# Source_Selector_V3.net
KiCad netlist of a schematic drawn in Altium Designer
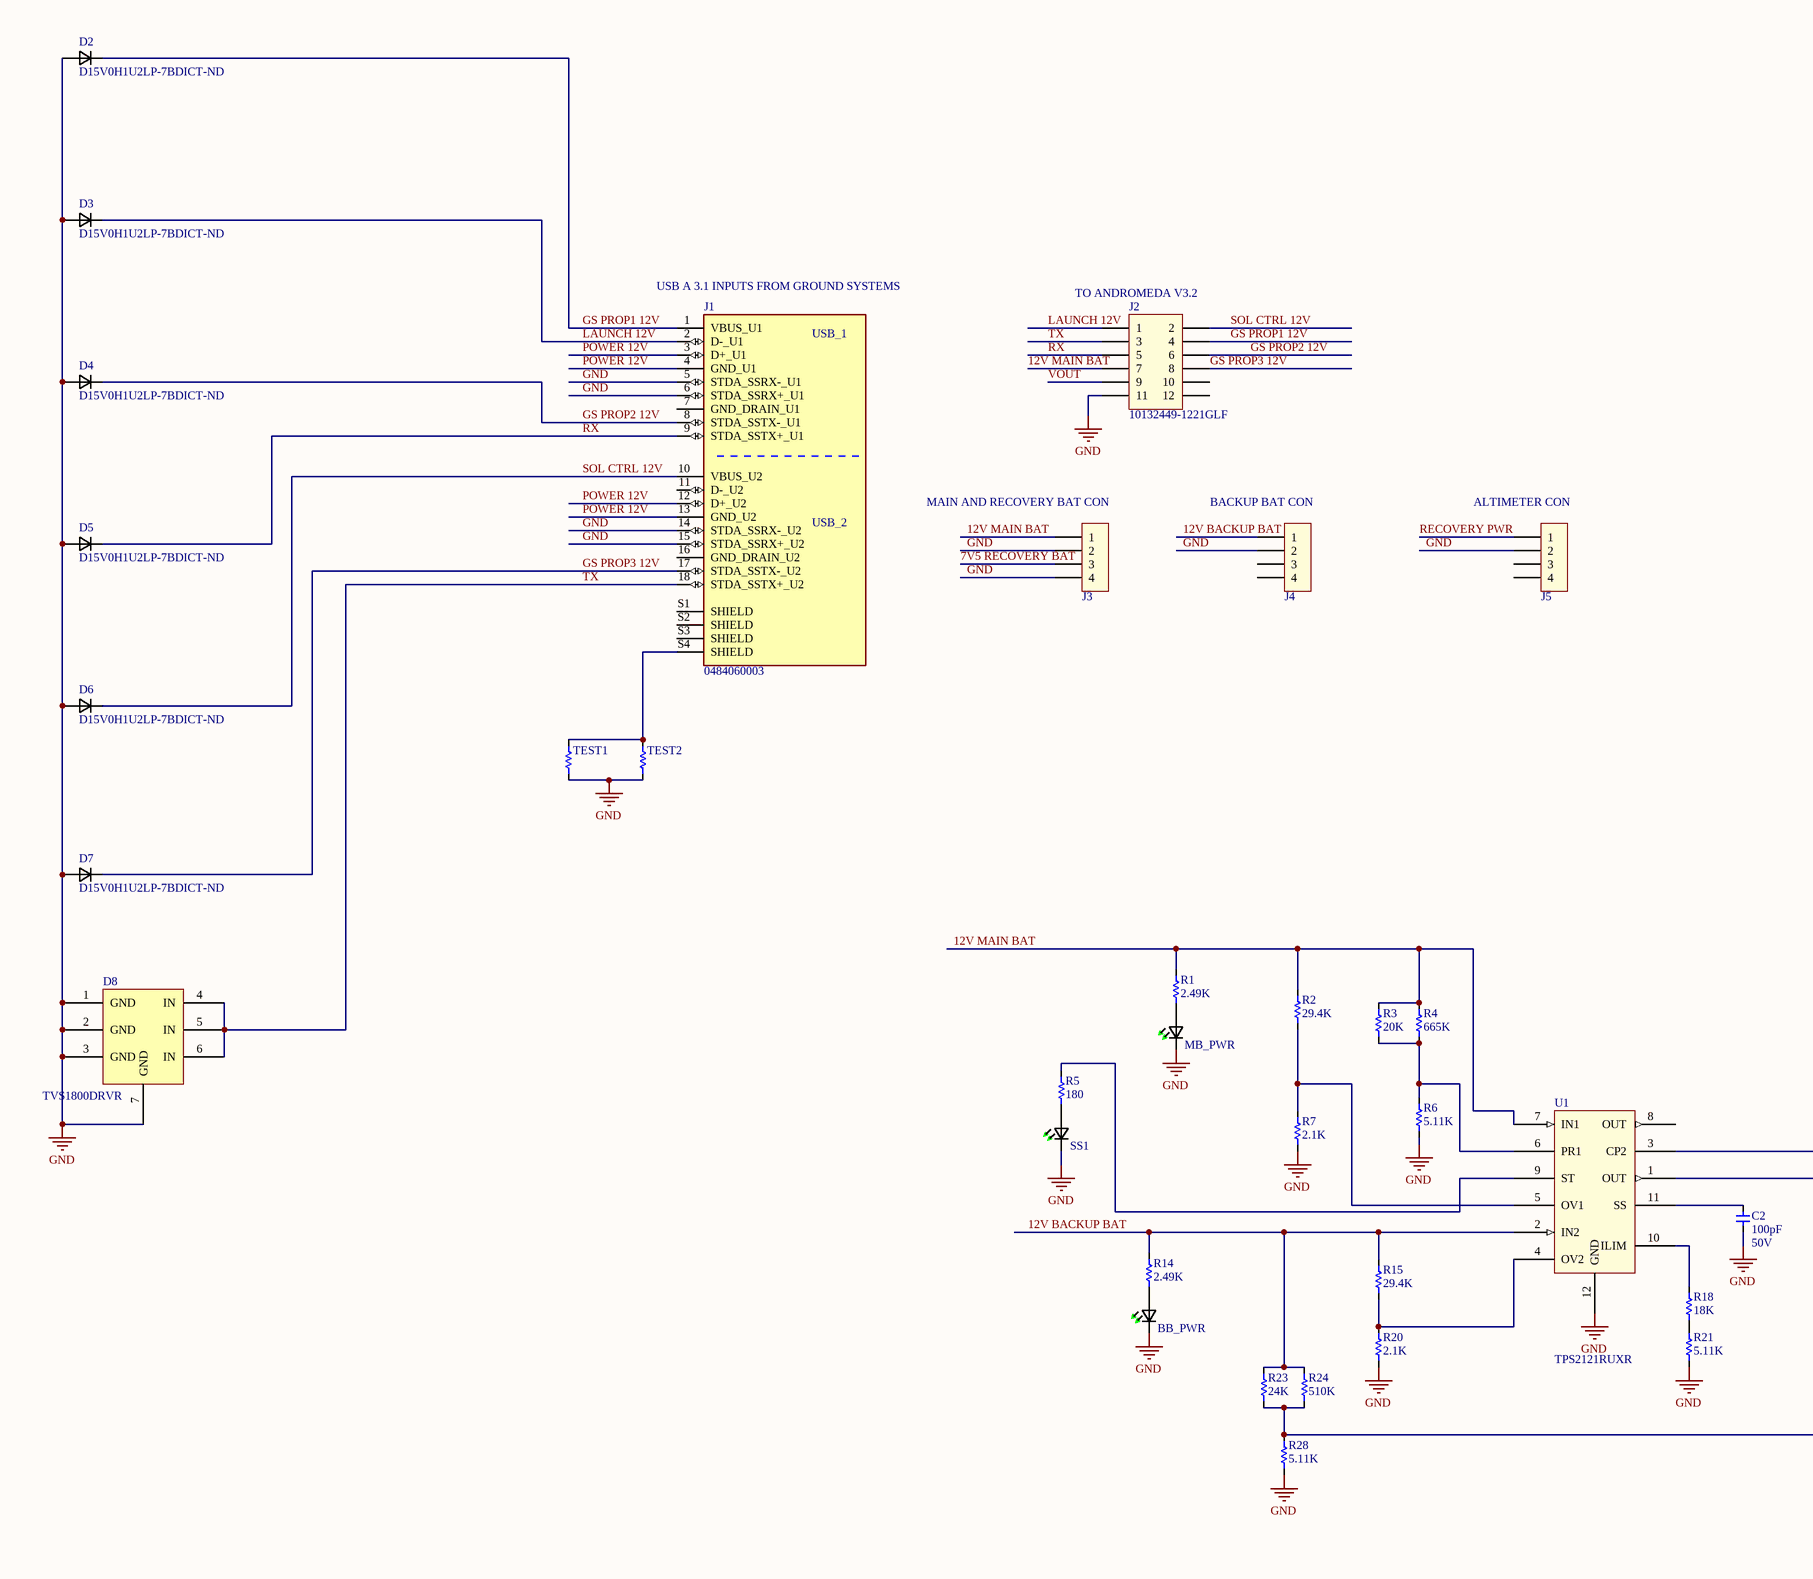
[diagram p0: Source_Selector_V3.SchDoc, left]
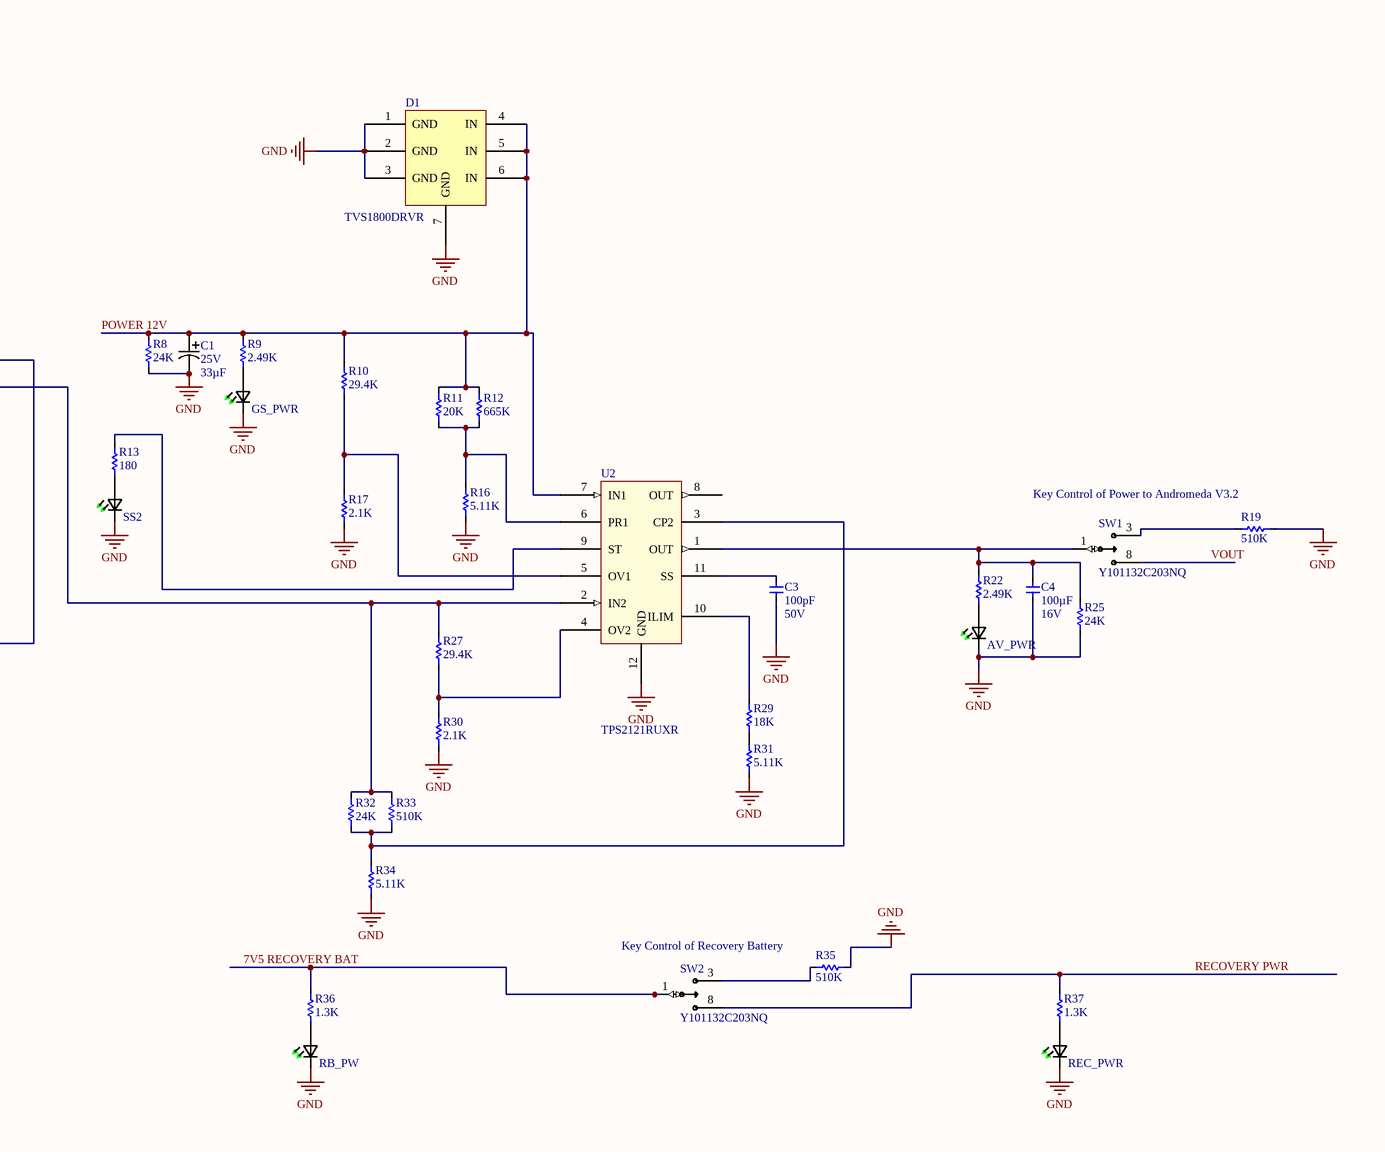
[diagram p1: Source_Selector_V3.SchDoc, right]

(export (version "E")
  (design (tool "Eeschema 10.0.6"))
  (components
    (comp (ref "AV_PWR")
      (value "LTST-C191KGKT")
      (footprint "LTST-C191KGKT")
      (description "LED GREEN CLEAR SMD 0603")
      (fields (field (name "MANUFACTURER") "Lite-On Inc."))
      (libsource (lib "Source Selector") (part "LTST-C191KGKT"))
    )
    (comp (ref "BB_PWR")
      (value "LTST-C191KGKT")
      (footprint "LTST-C191KGKT")
      (description "LED GREEN CLEAR SMD 0603")
      (fields (field (name "MANUFACTURER") "Lite-On Inc."))
      (libsource (lib "Source Selector") (part "LTST-C191KGKT"))
    )
    (comp (ref "C1")
      (value "UZG1E330MCL1GB")
      (footprint "PCAP_6.3x3-ELECT_NCA-M")
      (description "CAP ALUM 33UF 20% 25V SMD")
      (fields
        (field (name "MANUFACTURER") "Nichicon")
        (field (name "VOLTAGE") "25V")
        (field (name "CAPACITANCE") "33µF")
      )
      (libsource (lib "Source Selector") (part "UZG1E330MCL1GB"))
    )
    (comp (ref "C2")
      (value "04025A101JAT2A")
      (footprint "0603[1608]")
      (description "CAP CER 100PF 50V C0G/NP0 0402")
      (fields
        (field (name "MANUFACTURER") "AVX Corporation")
        (field (name "TOLERANCE") "±5%")
        (field (name "CAPACITANCE") "100pF")
        (field (name "VOLTAGE - RATED") "50V")
      )
      (libsource (lib "Source Selector") (part "04025A101JAT2A"))
    )
    (comp (ref "C3")
      (value "04025A101JAT2A")
      (footprint "0603[1608]")
      (description "CAP CER 100PF 50V C0G/NP0 0402")
      (fields
        (field (name "MANUFACTURER") "AVX Corporation")
        (field (name "TOLERANCE") "±5%")
        (field (name "CAPACITANCE") "100pF")
        (field (name "VOLTAGE - RATED") "50V")
      )
      (libsource (lib "Source Selector") (part "04025A101JAT2A"))
    )
    (comp (ref "C4")
      (value "EMK325ABJ107MM-P")
      (footprint "CAPC3225X280N")
      (description "CAP CER 100UF 16V X5R 1210")
      (fields
        (field (name "MANUFACTURER") "Taiyo Yuden")
        (field (name "TOLERANCE") "±20%")
        (field (name "CAPACITANCE") "100µF")
        (field (name "VOLTAGE - RATED") "16V")
      )
      (libsource (lib "Source Selector") (part "EMK325ABJ107MM-P"))
    )
    (comp (ref "D1")
      (value "TVS1800DRVR")
      (footprint "TVS1800DRVR")
      (description "UNIDIR PRECISION SURGE DIODE")
      (libsource (lib "Source Selector") (part "TVS1800DRVR"))
    )
    (comp (ref "D2")
      (value "D15V0H1U2LP-7B")
      (footprint "04025A101JAT2A")
      (description "TVS DIODE 15VWM 27VC DFN1006-2")
      (fields
        (field (name "MANUFACTURER") "Diodes Incorporated")
        (field (name "SUPPLIER PART NUMBER 1") "D15V0H1U2LP-7BDICT-ND")
      )
      (libsource (lib "Source Selector") (part "D15V0H1U2LP-7B"))
    )
    (comp (ref "D3")
      (value "D15V0H1U2LP-7B")
      (footprint "04025A101JAT2A")
      (description "TVS DIODE 15VWM 27VC DFN1006-2")
      (fields
        (field (name "MANUFACTURER") "Diodes Incorporated")
        (field (name "SUPPLIER PART NUMBER 1") "D15V0H1U2LP-7BDICT-ND")
      )
      (libsource (lib "Source Selector") (part "D15V0H1U2LP-7B"))
    )
    (comp (ref "D4")
      (value "D15V0H1U2LP-7B")
      (footprint "04025A101JAT2A")
      (description "TVS DIODE 15VWM 27VC DFN1006-2")
      (fields
        (field (name "MANUFACTURER") "Diodes Incorporated")
        (field (name "SUPPLIER PART NUMBER 1") "D15V0H1U2LP-7BDICT-ND")
      )
      (libsource (lib "Source Selector") (part "D15V0H1U2LP-7B"))
    )
    (comp (ref "D5")
      (value "D15V0H1U2LP-7B")
      (footprint "04025A101JAT2A")
      (description "TVS DIODE 15VWM 27VC DFN1006-2")
      (fields
        (field (name "MANUFACTURER") "Diodes Incorporated")
        (field (name "SUPPLIER PART NUMBER 1") "D15V0H1U2LP-7BDICT-ND")
      )
      (libsource (lib "Source Selector") (part "D15V0H1U2LP-7B"))
    )
    (comp (ref "D6")
      (value "D15V0H1U2LP-7B")
      (footprint "04025A101JAT2A")
      (description "TVS DIODE 15VWM 27VC DFN1006-2")
      (fields
        (field (name "MANUFACTURER") "Diodes Incorporated")
        (field (name "SUPPLIER PART NUMBER 1") "D15V0H1U2LP-7BDICT-ND")
      )
      (libsource (lib "Source Selector") (part "D15V0H1U2LP-7B"))
    )
    (comp (ref "D7")
      (value "D15V0H1U2LP-7B")
      (footprint "04025A101JAT2A")
      (description "TVS DIODE 15VWM 27VC DFN1006-2")
      (fields
        (field (name "MANUFACTURER") "Diodes Incorporated")
        (field (name "SUPPLIER PART NUMBER 1") "D15V0H1U2LP-7BDICT-ND")
      )
      (libsource (lib "Source Selector") (part "D15V0H1U2LP-7B"))
    )
    (comp (ref "D8")
      (value "TVS1800DRVR")
      (footprint "TVS1800DRVR")
      (description "UNIDIR PRECISION SURGE DIODE")
      (libsource (lib "Source Selector") (part "TVS1800DRVR"))
    )
    (comp (ref "GS_PWR")
      (value "LTST-C191KGKT")
      (footprint "LTST-C191KGKT")
      (description "LED GREEN CLEAR SMD 0603")
      (fields (field (name "MANUFACTURER") "Lite-On Inc."))
      (libsource (lib "Source Selector") (part "LTST-C191KGKT"))
    )
    (comp (ref "J1")
      (value "0484060003")
      (footprint "SnapEDApcb:MOLEX_0484060003")
      (fields (field (name "MF") "Molex"))
      (libsource (lib "Source Selector") (part "0484060003"))
    )
    (comp (ref "J2")
      (value "10132449-1221GLF")
      (footprint "10132449-1221GLF")
      (description "CONN HEADER R/A 12POS 3MM")
      (fields (field (name "MANUFACTURER") "Amphenol ICC (FCI)"))
      (libsource (lib "Source Selector") (part "10132449-1221GLF"))
    )
    (comp (ref "J3")
      (value "0430450400")
      (footprint "0430450400")
      (description "CONN HEADER R/A 4POS 3MM")
      (fields (field (name "MANUFACTURER") "Molex"))
      (libsource (lib "Source Selector") (part "0430450400"))
    )
    (comp (ref "J4")
      (value "0430450400")
      (footprint "0430450400")
      (description "CONN HEADER R/A 4POS 3MM")
      (fields (field (name "MANUFACTURER") "Molex"))
      (libsource (lib "Source Selector") (part "0430450400"))
    )
    (comp (ref "J5")
      (value "0430450400")
      (footprint "0430450400")
      (description "CONN HEADER R/A 4POS 3MM")
      (fields (field (name "MANUFACTURER") "Molex"))
      (libsource (lib "Source Selector") (part "0430450400"))
    )
    (comp (ref "MB_PWR")
      (value "LTST-C191KGKT")
      (footprint "LTST-C191KGKT")
      (description "LED GREEN CLEAR SMD 0603")
      (fields (field (name "MANUFACTURER") "Lite-On Inc."))
      (libsource (lib "Source Selector") (part "LTST-C191KGKT"))
    )
    (comp (ref "R1")
      (value "ERA-3AEB2491V")
      (footprint "0603[1608]")
      (description "RES SMD 2.49KOHM 0.1% 1/10W 0603")
      (fields
        (field (name "TOLERANCE") "±0.1%")
        (field (name "MANUFACTURER") "Panasonic Electronic Components")
        (field (name "RESISTANCE") "2.49K")
      )
      (libsource (lib "Source Selector") (part "ERA-3AEB2491V"))
    )
    (comp (ref "R2")
      (value "RMCF0603FT29K4")
      (footprint "0603[1608]")
      (description "RES 29.4K OHM 1% 1/10W 0603")
      (fields
        (field (name "TOLERANCE") "±1%")
        (field (name "MANUFACTURER") "Stackpole Electronics Inc")
        (field (name "RESISTANCE") "29.4K")
      )
      (libsource (lib "Source Selector") (part "RMCF0603FT29K4"))
    )
    (comp (ref "R3")
      (value "RNCF0603BTC20K0")
      (footprint "0603[1608]")
      (description "RES 20K OHM 0.1% 1/10W 0603")
      (fields
        (field (name "TOLERANCE") "±0.1%")
        (field (name "MANUFACTURER") "Stackpole Electronics Inc")
        (field (name "RESISTANCE") "20K")
      )
      (libsource (lib "Source Selector") (part "RNCF0603BTC20K0"))
    )
    (comp (ref "R4")
      (value "RMCF0603FT665K")
      (footprint "0603[1608]")
      (description "RES 665K OHM 1% 1/10W 0603")
      (fields
        (field (name "TOLERANCE") "±1%")
        (field (name "MANUFACTURER") "Stackpole Electronics Inc")
        (field (name "RESISTANCE") "665K")
      )
      (libsource (lib "Source Selector") (part "RMCF0603FT665K"))
    )
    (comp (ref "R5")
      (value "CRGCQ0603F180R")
      (footprint "0603[1608]")
      (description "RES 180 OHM 1% 1/10W 0603")
      (fields
        (field (name "TOLERANCE") "±0.1%")
        (field (name "MANUFACTURER") "TE Connectivity Passive Product")
        (field (name "RESISTANCE") "180")
      )
      (libsource (lib "Source Selector") (part "CRGCQ0603F180R"))
    )
    (comp (ref "R6")
      (value "RT0603BRD075K11L")
      (footprint "0603[1608]")
      (description "RES SMD 5.11KOHM 0.1% 1/10W 0603")
      (fields
        (field (name "TOLERANCE") "±0.1%")
        (field (name "MANUFACTURER") "Yageo")
        (field (name "RESISTANCE") "5.11K")
      )
      (libsource (lib "Source Selector") (part "RT0603BRD075K11L"))
    )
    (comp (ref "R7")
      (value "RQ73C1J2K1BTD")
      (footprint "0603[1608]")
      (description "RES 2.1 KOHMS 0.1% 0.15W 0603")
      (fields
        (field (name "TOLERANCE") "±0.1%")
        (field (name "MANUFACTURER") "TE Connectivity Passive Product")
        (field (name "RESISTANCE") "2.1K")
      )
      (libsource (lib "Source Selector") (part "RQ73C1J2K1BTD"))
    )
    (comp (ref "R8")
      (value "RT0603BRD0724KL")
      (footprint "0603[1608]")
      (description "RES SMD 24K OHM 0.1% 1/10W 0603")
      (fields
        (field (name "TOLERANCE") "±0.1%")
        (field (name "MANUFACTURER") "Yageo")
        (field (name "RESISTANCE") "24K")
      )
      (libsource (lib "Source Selector") (part "RT0603BRD0724KL"))
    )
    (comp (ref "R9")
      (value "ERA-3AEB2491V")
      (footprint "0603[1608]")
      (description "RES SMD 2.49KOHM 0.1% 1/10W 0603")
      (fields
        (field (name "TOLERANCE") "±0.1%")
        (field (name "MANUFACTURER") "Panasonic Electronic Components")
        (field (name "RESISTANCE") "2.49K")
      )
      (libsource (lib "Source Selector") (part "ERA-3AEB2491V"))
    )
    (comp (ref "R10")
      (value "RMCF0603FT29K4")
      (footprint "0603[1608]")
      (description "RES 29.4K OHM 1% 1/10W 0603")
      (fields
        (field (name "TOLERANCE") "±1%")
        (field (name "MANUFACTURER") "Stackpole Electronics Inc")
        (field (name "RESISTANCE") "29.4K")
      )
      (libsource (lib "Source Selector") (part "RMCF0603FT29K4"))
    )
    (comp (ref "R11")
      (value "RNCF0603BTC20K0")
      (footprint "0603[1608]")
      (description "RES 20K OHM 0.1% 1/10W 0603")
      (fields
        (field (name "TOLERANCE") "±0.1%")
        (field (name "MANUFACTURER") "Stackpole Electronics Inc")
        (field (name "RESISTANCE") "20K")
      )
      (libsource (lib "Source Selector") (part "RNCF0603BTC20K0"))
    )
    (comp (ref "R12")
      (value "RMCF0603FT665K")
      (footprint "0603[1608]")
      (description "RES 665K OHM 1% 1/10W 0603")
      (fields
        (field (name "TOLERANCE") "±1%")
        (field (name "MANUFACTURER") "Stackpole Electronics Inc")
        (field (name "RESISTANCE") "665K")
      )
      (libsource (lib "Source Selector") (part "RMCF0603FT665K"))
    )
    (comp (ref "R13")
      (value "CRGCQ0603F180R")
      (footprint "0603[1608]")
      (description "RES 180 OHM 1% 1/10W 0603")
      (fields
        (field (name "TOLERANCE") "±0.1%")
        (field (name "MANUFACTURER") "TE Connectivity Passive Product")
        (field (name "RESISTANCE") "180")
      )
      (libsource (lib "Source Selector") (part "CRGCQ0603F180R"))
    )
    (comp (ref "R14")
      (value "ERA-3AEB2491V")
      (footprint "0603[1608]")
      (description "RES SMD 2.49KOHM 0.1% 1/10W 0603")
      (fields
        (field (name "TOLERANCE") "±0.1%")
        (field (name "MANUFACTURER") "Panasonic Electronic Components")
        (field (name "RESISTANCE") "2.49K")
      )
      (libsource (lib "Source Selector") (part "ERA-3AEB2491V"))
    )
    (comp (ref "R15")
      (value "RMCF0603FT29K4")
      (footprint "0603[1608]")
      (description "RES 29.4K OHM 1% 1/10W 0603")
      (fields
        (field (name "TOLERANCE") "±1%")
        (field (name "MANUFACTURER") "Stackpole Electronics Inc")
        (field (name "RESISTANCE") "29.4K")
      )
      (libsource (lib "Source Selector") (part "RMCF0603FT29K4"))
    )
    (comp (ref "R16")
      (value "RT0603BRD075K11L")
      (footprint "0603[1608]")
      (description "RES SMD 5.11KOHM 0.1% 1/10W 0603")
      (fields
        (field (name "TOLERANCE") "±0.1%")
        (field (name "MANUFACTURER") "Yageo")
        (field (name "RESISTANCE") "5.11K")
      )
      (libsource (lib "Source Selector") (part "RT0603BRD075K11L"))
    )
    (comp (ref "R17")
      (value "RQ73C1J2K1BTD")
      (footprint "0603[1608]")
      (description "RES 2.1 KOHMS 0.1% 0.15W 0603")
      (fields
        (field (name "TOLERANCE") "±0.1%")
        (field (name "MANUFACTURER") "TE Connectivity Passive Product")
        (field (name "RESISTANCE") "2.1K")
      )
      (libsource (lib "Source Selector") (part "RQ73C1J2K1BTD"))
    )
    (comp (ref "R18")
      (value "RT0603BRE0718KL")
      (footprint "0603[1608]")
      (description "RES SMD 18K OHM 0.1% 1/10W 0603")
      (fields
        (field (name "TOLERANCE") "±0.1%")
        (field (name "MANUFACTURER") "Yageo")
        (field (name "RESISTANCE") "18K")
      )
      (libsource (lib "Source Selector") (part "RT0603BRE0718KL"))
    )
    (comp (ref "R19")
      (value "CPF0603B510KE1")
      (footprint "0603[1608]")
      (description "RES SMD 510K OHM 0.1% 1/16W 0603")
      (fields
        (field (name "TOLERANCE") "±0.1%")
        (field (name "MANUFACTURER") "TE Connectivity Passive Product")
        (field (name "RESISTANCE") "510K")
      )
      (libsource (lib "Source Selector") (part "CPF0603B510KE1"))
    )
    (comp (ref "R20")
      (value "RQ73C1J2K1BTD")
      (footprint "0603[1608]")
      (description "RES 2.1 KOHMS 0.1% 0.15W 0603")
      (fields
        (field (name "TOLERANCE") "±0.1%")
        (field (name "MANUFACTURER") "TE Connectivity Passive Product")
        (field (name "RESISTANCE") "2.1K")
      )
      (libsource (lib "Source Selector") (part "RQ73C1J2K1BTD"))
    )
    (comp (ref "R21")
      (value "RT0603BRD075K11L")
      (footprint "0603[1608]")
      (description "RES SMD 5.11KOHM 0.1% 1/10W 0603")
      (fields
        (field (name "TOLERANCE") "±0.1%")
        (field (name "MANUFACTURER") "Yageo")
        (field (name "RESISTANCE") "5.11K")
      )
      (libsource (lib "Source Selector") (part "RT0603BRD075K11L"))
    )
    (comp (ref "R22")
      (value "ERA-3AEB2491V")
      (footprint "0603[1608]")
      (description "RES SMD 2.49KOHM 0.1% 1/10W 0603")
      (fields
        (field (name "TOLERANCE") "±0.1%")
        (field (name "MANUFACTURER") "Panasonic Electronic Components")
        (field (name "RESISTANCE") "2.49K")
      )
      (libsource (lib "Source Selector") (part "ERA-3AEB2491V"))
    )
    (comp (ref "R23")
      (value "RT0603BRD0724KL")
      (footprint "0603[1608]")
      (description "RES SMD 24K OHM 0.1% 1/10W 0603")
      (fields
        (field (name "TOLERANCE") "±0.1%")
        (field (name "MANUFACTURER") "Yageo")
        (field (name "RESISTANCE") "24K")
      )
      (libsource (lib "Source Selector") (part "RT0603BRD0724KL"))
    )
    (comp (ref "R24")
      (value "CPF0603B510KE1")
      (footprint "0603[1608]")
      (description "RES SMD 510K OHM 0.1% 1/16W 0603")
      (fields
        (field (name "TOLERANCE") "±0.1%")
        (field (name "MANUFACTURER") "TE Connectivity Passive Product")
        (field (name "RESISTANCE") "510K")
      )
      (libsource (lib "Source Selector") (part "CPF0603B510KE1"))
    )
    (comp (ref "R25")
      (value "RT0603BRD0724KL")
      (footprint "0603[1608]")
      (description "RES SMD 24K OHM 0.1% 1/10W 0603")
      (fields
        (field (name "TOLERANCE") "±0.1%")
        (field (name "MANUFACTURER") "Yageo")
        (field (name "RESISTANCE") "24K")
      )
      (libsource (lib "Source Selector") (part "RT0603BRD0724KL"))
    )
    (comp (ref "R27")
      (value "RMCF0603FT29K4")
      (footprint "0603[1608]")
      (description "RES 29.4K OHM 1% 1/10W 0603")
      (fields
        (field (name "TOLERANCE") "±1%")
        (field (name "MANUFACTURER") "Stackpole Electronics Inc")
        (field (name "RESISTANCE") "29.4K")
      )
      (libsource (lib "Source Selector") (part "RMCF0603FT29K4"))
    )
    (comp (ref "R28")
      (value "RT0603BRD075K11L")
      (footprint "0603[1608]")
      (description "RES SMD 5.11KOHM 0.1% 1/10W 0603")
      (fields
        (field (name "TOLERANCE") "±0.1%")
        (field (name "MANUFACTURER") "Yageo")
        (field (name "RESISTANCE") "5.11K")
      )
      (libsource (lib "Source Selector") (part "RT0603BRD075K11L"))
    )
    (comp (ref "R29")
      (value "RT0603BRE0718KL")
      (footprint "0603[1608]")
      (description "RES SMD 18K OHM 0.1% 1/10W 0603")
      (fields
        (field (name "TOLERANCE") "±0.1%")
        (field (name "MANUFACTURER") "Yageo")
        (field (name "RESISTANCE") "18K")
      )
      (libsource (lib "Source Selector") (part "RT0603BRE0718KL"))
    )
    (comp (ref "R30")
      (value "RQ73C1J2K1BTD")
      (footprint "0603[1608]")
      (description "RES 2.1 KOHMS 0.1% 0.15W 0603")
      (fields
        (field (name "TOLERANCE") "±0.1%")
        (field (name "MANUFACTURER") "TE Connectivity Passive Product")
        (field (name "RESISTANCE") "2.1K")
      )
      (libsource (lib "Source Selector") (part "RQ73C1J2K1BTD"))
    )
    (comp (ref "R31")
      (value "RT0603BRD075K11L")
      (footprint "0603[1608]")
      (description "RES SMD 5.11KOHM 0.1% 1/10W 0603")
      (fields
        (field (name "TOLERANCE") "±0.1%")
        (field (name "MANUFACTURER") "Yageo")
        (field (name "RESISTANCE") "5.11K")
      )
      (libsource (lib "Source Selector") (part "RT0603BRD075K11L"))
    )
    (comp (ref "R32")
      (value "RT0603BRD0724KL")
      (footprint "0603[1608]")
      (description "RES SMD 24K OHM 0.1% 1/10W 0603")
      (fields
        (field (name "TOLERANCE") "±0.1%")
        (field (name "MANUFACTURER") "Yageo")
        (field (name "RESISTANCE") "24K")
      )
      (libsource (lib "Source Selector") (part "RT0603BRD0724KL"))
    )
    (comp (ref "R33")
      (value "CPF0603B510KE1")
      (footprint "0603[1608]")
      (description "RES SMD 510K OHM 0.1% 1/16W 0603")
      (fields
        (field (name "TOLERANCE") "±0.1%")
        (field (name "MANUFACTURER") "TE Connectivity Passive Product")
        (field (name "RESISTANCE") "510K")
      )
      (libsource (lib "Source Selector") (part "CPF0603B510KE1"))
    )
    (comp (ref "R34")
      (value "RT0603BRD075K11L")
      (footprint "0603[1608]")
      (description "RES SMD 5.11KOHM 0.1% 1/10W 0603")
      (fields
        (field (name "TOLERANCE") "±0.1%")
        (field (name "MANUFACTURER") "Yageo")
        (field (name "RESISTANCE") "5.11K")
      )
      (libsource (lib "Source Selector") (part "RT0603BRD075K11L"))
    )
    (comp (ref "R35")
      (value "CPF0603B510KE1")
      (footprint "0603[1608]")
      (description "RES SMD 510K OHM 0.1% 1/16W 0603")
      (fields
        (field (name "TOLERANCE") "±0.1%")
        (field (name "MANUFACTURER") "TE Connectivity Passive Product")
        (field (name "RESISTANCE") "510K")
      )
      (libsource (lib "Source Selector") (part "CPF0603B510KE1"))
    )
    (comp (ref "R36")
      (value "MCT06030C1301FP500")
      (footprint "0603[1608]")
      (description "RES SMD 1.3K OHM 1% 1/8W 0603")
      (fields
        (field (name "TOLERANCE") "±1%")
        (field (name "MANUFACTURER") "Vishay Beyschlag")
        (field (name "RESISTANCE") "1.3K")
      )
      (libsource (lib "Source Selector") (part "MCT06030C1301FP500"))
    )
    (comp (ref "R37")
      (value "MCT06030C1301FP500")
      (footprint "0603[1608]")
      (description "RES SMD 1.3K OHM 1% 1/8W 0603")
      (fields
        (field (name "TOLERANCE") "±1%")
        (field (name "MANUFACTURER") "Vishay Beyschlag")
        (field (name "RESISTANCE") "1.3K")
      )
      (libsource (lib "Source Selector") (part "MCT06030C1301FP500"))
    )
    (comp (ref "RB_PW")
      (value "LTST-C191KGKT")
      (footprint "LTST-C191KGKT")
      (description "LED GREEN CLEAR SMD 0603")
      (fields (field (name "MANUFACTURER") "Lite-On Inc."))
      (libsource (lib "Source Selector") (part "LTST-C191KGKT"))
    )
    (comp (ref "REC_PWR")
      (value "LTST-C191KGKT")
      (footprint "LTST-C191KGKT")
      (description "LED GREEN CLEAR SMD 0603")
      (fields (field (name "MANUFACTURER") "Lite-On Inc."))
      (libsource (lib "Source Selector") (part "LTST-C191KGKT"))
    )
    (comp (ref "SS1")
      (value "LTST-C191KGKT")
      (footprint "LTST-C191KGKT")
      (description "LED GREEN CLEAR SMD 0603")
      (fields (field (name "MANUFACTURER") "Lite-On Inc."))
      (libsource (lib "Source Selector") (part "LTST-C191KGKT"))
    )
    (comp (ref "SS2")
      (value "LTST-C191KGKT")
      (footprint "LTST-C191KGKT")
      (description "LED GREEN CLEAR SMD 0603")
      (fields (field (name "MANUFACTURER") "Lite-On Inc."))
      (libsource (lib "Source Selector") (part "LTST-C191KGKT"))
    )
    (comp (ref "SW1")
      (value "Y101132C203NQ")
      (footprint "Y101132C203NQ")
      (description "SWITCH KEYLOCK 2POS SPDT 4A 125V")
      (fields (field (name "MANUFACTURER") "C&K"))
      (libsource (lib "Source Selector") (part "Y101132C203NQ"))
    )
    (comp (ref "SW2")
      (value "Y101132C203NQ")
      (footprint "Y101132C203NQ")
      (description "SWITCH KEYLOCK 2POS SPDT 4A 125V")
      (fields (field (name "MANUFACTURER") "C&K"))
      (libsource (lib "Source Selector") (part "Y101132C203NQ"))
    )
    (comp (ref "TEST1")
      (value "RQ73C1J2K1BTD")
      (footprint "0603[1608]")
      (description "RES 2.1 KOHMS 0.1% 0.15W 0603")
      (fields
        (field (name "TOLERANCE") "±0.1%")
        (field (name "MANUFACTURER") "TE Connectivity Passive Product")
      )
      (libsource (lib "Source Selector") (part "RQ73C1J2K1BTD"))
    )
    (comp (ref "TEST2")
      (value "RQ73C1J2K1BTD")
      (footprint "0603[1608]")
      (description "RES 2.1 KOHMS 0.1% 0.15W 0603")
      (fields
        (field (name "TOLERANCE") "±0.1%")
        (field (name "MANUFACTURER") "TE Connectivity Passive Product")
      )
      (libsource (lib "Source Selector") (part "RQ73C1J2K1BTD"))
    )
    (comp (ref "U1")
      (value "TPS2121RUXR")
      (footprint "IC_TPS2121RUXR")
      (description "PWR MGMT BATTERY MGMT")
      (libsource (lib "Source Selector") (part "TPS2121RUXR"))
    )
    (comp (ref "U2")
      (value "TPS2121RUXR")
      (footprint "IC_TPS2121RUXR")
      (description "PWR MGMT BATTERY MGMT")
      (libsource (lib "Source Selector") (part "TPS2121RUXR"))
    )
  )
  (nets
    (net (code "1") (name "/7V5 RECOVERY BAT") (class "Default")
      (node (ref "J3") (pin "3") (pinfunction "3_3") (pintype "passive"))
      (node (ref "R36") (pin "2") (pinfunction "2_2") (pintype "passive"))
      (node (ref "SW2") (pin "1") (pinfunction "1_1") (pintype "bidirectional"))
    )
    (net (code "2") (name "/12V BACKUP BAT") (class "Default")
      (node (ref "J4") (pin "1") (pinfunction "1_1") (pintype "passive"))
      (node (ref "R14") (pin "2") (pinfunction "2_2") (pintype "passive"))
      (node (ref "R15") (pin "2") (pinfunction "2_2") (pintype "passive"))
      (node (ref "R23") (pin "2") (pinfunction "2_2") (pintype "passive"))
      (node (ref "R24") (pin "2") (pinfunction "2_2") (pintype "passive"))
      (node (ref "U1") (pin "2") (pinfunction "IN2_2") (pintype "input"))
    )
    (net (code "3") (name "/12V MAIN BAT") (class "Default")
      (node (ref "J2") (pin "7") (pinfunction "7_7") (pintype "passive"))
      (node (ref "J3") (pin "1") (pinfunction "1_1") (pintype "passive"))
      (node (ref "R1") (pin "2") (pinfunction "2_2") (pintype "passive"))
      (node (ref "R2") (pin "2") (pinfunction "2_2") (pintype "passive"))
      (node (ref "R3") (pin "2") (pinfunction "2_2") (pintype "passive"))
      (node (ref "R4") (pin "2") (pinfunction "2_2") (pintype "passive"))
      (node (ref "U1") (pin "7") (pinfunction "IN1_7") (pintype "input"))
    )
    (net (code "4") (name "/GS PROP1 12V") (class "Default")
      (node (ref "D2") (pin "1") (pinfunction "K2_1") (pintype "passive"))
      (node (ref "J1") (pin "1") (pinfunction "VBUS_U1_1") (pintype "power_in"))
      (node (ref "J2") (pin "4") (pinfunction "4_4") (pintype "passive"))
    )
    (net (code "5") (name "/GS PROP2 12V") (class "Default")
      (node (ref "D4") (pin "1") (pinfunction "K2_1") (pintype "passive"))
      (node (ref "J1") (pin "8") (pinfunction "STDA_SSTX-_U1_8") (pintype "bidirectional"))
      (node (ref "J2") (pin "6") (pinfunction "6_6") (pintype "passive"))
    )
    (net (code "6") (name "/GS PROP3 12V") (class "Default")
      (node (ref "D7") (pin "1") (pinfunction "K2_1") (pintype "passive"))
      (node (ref "J1") (pin "17") (pinfunction "STDA_SSTX-_U2_17") (pintype "bidirectional"))
      (node (ref "J2") (pin "8") (pinfunction "8_8") (pintype "passive"))
    )
    (net (code "7") (name "/LAUNCH 12V") (class "Default")
      (node (ref "D3") (pin "1") (pinfunction "K2_1") (pintype "passive"))
      (node (ref "J1") (pin "2") (pinfunction "D-_U1_2") (pintype "bidirectional"))
      (node (ref "J2") (pin "1") (pinfunction "1_1") (pintype "passive"))
    )
    (net (code "8") (name "/POWER 12V") (class "Default")
      (node (ref "C1") (pin "1") (pinfunction "1_1") (pintype "passive"))
      (node (ref "D1") (pin "4") (pinfunction "IN_4") (pintype "passive"))
      (node (ref "D1") (pin "5") (pinfunction "IN_5") (pintype "passive"))
      (node (ref "D1") (pin "6") (pinfunction "IN_6") (pintype "passive"))
      (node (ref "J1") (pin "12") (pinfunction "D+_U2_12") (pintype "bidirectional"))
      (node (ref "J1") (pin "13") (pinfunction "GND_U2_13") (pintype "power_in"))
      (node (ref "J1") (pin "3") (pinfunction "D+_U1_3") (pintype "bidirectional"))
      (node (ref "J1") (pin "4") (pinfunction "GND_U1_4") (pintype "power_in"))
      (node (ref "R10") (pin "2") (pinfunction "2_2") (pintype "passive"))
      (node (ref "R11") (pin "2") (pinfunction "2_2") (pintype "passive"))
      (node (ref "R12") (pin "2") (pinfunction "2_2") (pintype "passive"))
      (node (ref "R8") (pin "2") (pinfunction "2_2") (pintype "passive"))
      (node (ref "R9") (pin "2") (pinfunction "2_2") (pintype "passive"))
      (node (ref "U2") (pin "7") (pinfunction "IN1_7") (pintype "input"))
    )
    (net (code "9") (name "/RECOVERY PWR") (class "Default")
      (node (ref "J5") (pin "1") (pinfunction "1_1") (pintype "passive"))
      (node (ref "R37") (pin "2") (pinfunction "2_2") (pintype "passive"))
      (node (ref "SW2") (pin "8") (pinfunction "8_8") (pintype "power_in"))
    )
    (net (code "10") (name "/RX") (class "Default")
      (node (ref "D5") (pin "1") (pinfunction "K2_1") (pintype "passive"))
      (node (ref "J1") (pin "9") (pinfunction "STDA_SSTX+_U1_9") (pintype "bidirectional"))
      (node (ref "J2") (pin "5") (pinfunction "5_5") (pintype "passive"))
    )
    (net (code "11") (name "/SOL CTRL 12V") (class "Default")
      (node (ref "D6") (pin "1") (pinfunction "K2_1") (pintype "passive"))
      (node (ref "J1") (pin "10") (pinfunction "VBUS_U2_10") (pintype "power_in"))
      (node (ref "J2") (pin "2") (pinfunction "2_2") (pintype "passive"))
    )
    (net (code "12") (name "/TX") (class "Default")
      (node (ref "D8") (pin "4") (pinfunction "IN_4") (pintype "passive"))
      (node (ref "D8") (pin "5") (pinfunction "IN_5") (pintype "passive"))
      (node (ref "D8") (pin "6") (pinfunction "IN_6") (pintype "passive"))
      (node (ref "J1") (pin "18") (pinfunction "STDA_SSTX+_U2_18") (pintype "bidirectional"))
      (node (ref "J2") (pin "3") (pinfunction "3_3") (pintype "passive"))
    )
    (net (code "13") (name "/VOUT") (class "Default")
      (node (ref "J2") (pin "9") (pinfunction "9_9") (pintype "passive"))
      (node (ref "SW1") (pin "8") (pinfunction "8_8") (pintype "power_in"))
    )
    (net (code "14") (name "GND") (class "Default")
      (node (ref "AV_PWR") (pin "1") (pinfunction "K2_1") (pintype "passive"))
      (node (ref "BB_PWR") (pin "1") (pinfunction "K2_1") (pintype "passive"))
      (node (ref "C1") (pin "2") (pinfunction "2_2") (pintype "passive"))
      (node (ref "C2") (pin "1") (pinfunction "1_1") (pintype "passive"))
      (node (ref "C3") (pin "1") (pinfunction "1_1") (pintype "passive"))
      (node (ref "C4") (pin "1") (pinfunction "1_1") (pintype "passive"))
      (node (ref "D1") (pin "1") (pinfunction "GND_1") (pintype "passive"))
      (node (ref "D1") (pin "2") (pinfunction "GND_2") (pintype "passive"))
      (node (ref "D1") (pin "3") (pinfunction "GND_3") (pintype "passive"))
      (node (ref "D1") (pin "7") (pinfunction "GND_7") (pintype "passive"))
      (node (ref "D2") (pin "2") (pinfunction "A2_2") (pintype "passive"))
      (node (ref "D3") (pin "2") (pinfunction "A2_2") (pintype "passive"))
      (node (ref "D4") (pin "2") (pinfunction "A2_2") (pintype "passive"))
      (node (ref "D5") (pin "2") (pinfunction "A2_2") (pintype "passive"))
      (node (ref "D6") (pin "2") (pinfunction "A2_2") (pintype "passive"))
      (node (ref "D7") (pin "2") (pinfunction "A2_2") (pintype "passive"))
      (node (ref "D8") (pin "1") (pinfunction "GND_1") (pintype "passive"))
      (node (ref "D8") (pin "2") (pinfunction "GND_2") (pintype "passive"))
      (node (ref "D8") (pin "3") (pinfunction "GND_3") (pintype "passive"))
      (node (ref "D8") (pin "7") (pinfunction "GND_7") (pintype "passive"))
      (node (ref "GS_PWR") (pin "1") (pinfunction "K2_1") (pintype "passive"))
      (node (ref "J1") (pin "14") (pinfunction "STDA_SSRX-_U2_14") (pintype "bidirectional"))
      (node (ref "J1") (pin "15") (pinfunction "STDA_SSRX+_U2_15") (pintype "bidirectional"))
      (node (ref "J1") (pin "5") (pinfunction "STDA_SSRX-_U1_5") (pintype "bidirectional"))
      (node (ref "J1") (pin "6") (pinfunction "STDA_SSRX+_U1_6") (pintype "bidirectional"))
      (node (ref "J2") (pin "11") (pinfunction "11_11") (pintype "passive"))
      (node (ref "J3") (pin "2") (pinfunction "2_2") (pintype "passive"))
      (node (ref "J3") (pin "4") (pinfunction "4_4") (pintype "passive"))
      (node (ref "J4") (pin "2") (pinfunction "2_2") (pintype "passive"))
      (node (ref "J5") (pin "2") (pinfunction "2_2") (pintype "passive"))
      (node (ref "MB_PWR") (pin "1") (pinfunction "K2_1") (pintype "passive"))
      (node (ref "R16") (pin "1") (pinfunction "1_1") (pintype "passive"))
      (node (ref "R17") (pin "1") (pinfunction "1_1") (pintype "passive"))
      (node (ref "R19") (pin "1") (pinfunction "1_1") (pintype "passive"))
      (node (ref "R20") (pin "1") (pinfunction "1_1") (pintype "passive"))
      (node (ref "R21") (pin "1") (pinfunction "1_1") (pintype "passive"))
      (node (ref "R25") (pin "1") (pinfunction "1_1") (pintype "passive"))
      (node (ref "R28") (pin "1") (pinfunction "1_1") (pintype "passive"))
      (node (ref "R30") (pin "1") (pinfunction "1_1") (pintype "passive"))
      (node (ref "R31") (pin "1") (pinfunction "1_1") (pintype "passive"))
      (node (ref "R34") (pin "1") (pinfunction "1_1") (pintype "passive"))
      (node (ref "R35") (pin "1") (pinfunction "1_1") (pintype "passive"))
      (node (ref "R6") (pin "1") (pinfunction "1_1") (pintype "passive"))
      (node (ref "R7") (pin "1") (pinfunction "1_1") (pintype "passive"))
      (node (ref "R8") (pin "1") (pinfunction "1_1") (pintype "passive"))
      (node (ref "RB_PW") (pin "1") (pinfunction "K2_1") (pintype "passive"))
      (node (ref "REC_PWR") (pin "1") (pinfunction "K2_1") (pintype "passive"))
      (node (ref "SS1") (pin "1") (pinfunction "K2_1") (pintype "passive"))
      (node (ref "SS2") (pin "1") (pinfunction "K2_1") (pintype "passive"))
      (node (ref "TEST1") (pin "1") (pinfunction "1_1") (pintype "passive"))
      (node (ref "TEST2") (pin "1") (pinfunction "1_1") (pintype "passive"))
      (node (ref "U1") (pin "12") (pinfunction "GND_12") (pintype "passive"))
      (node (ref "U2") (pin "12") (pinfunction "GND_12") (pintype "passive"))
    )
    (net (code "15") (name "Net-(AV_PWR-A2)") (class "Default")
      (node (ref "AV_PWR") (pin "2") (pinfunction "A2_2") (pintype "passive"))
      (node (ref "R22") (pin "1") (pinfunction "1_1") (pintype "passive"))
    )
    (net (code "16") (name "Net-(BB_PWR-A2)") (class "Default")
      (node (ref "BB_PWR") (pin "2") (pinfunction "A2_2") (pintype "passive"))
      (node (ref "R14") (pin "1") (pinfunction "1_1") (pintype "passive"))
    )
    (net (code "17") (name "Net-(C4-Pad2)") (class "Default")
      (node (ref "C4") (pin "2") (pinfunction "2_2") (pintype "passive"))
      (node (ref "R22") (pin "2") (pinfunction "2_2") (pintype "passive"))
      (node (ref "R25") (pin "2") (pinfunction "2_2") (pintype "passive"))
      (node (ref "SW1") (pin "1") (pinfunction "1_1") (pintype "bidirectional"))
      (node (ref "U2") (pin "1") (pinfunction "OUT_1") (pintype "output"))
    )
    (net (code "18") (name "Net-(GS_PWR-A2)") (class "Default")
      (node (ref "GS_PWR") (pin "2") (pinfunction "A2_2") (pintype "passive"))
      (node (ref "R9") (pin "1") (pinfunction "1_1") (pintype "passive"))
    )
    (net (code "19") (name "Net-(J1-SHIELD-PadS4)") (class "Default")
      (node (ref "J1") (pin "S4") (pinfunction "SHIELD_S4") (pintype "passive"))
      (node (ref "TEST1") (pin "2") (pinfunction "2_2") (pintype "passive"))
      (node (ref "TEST2") (pin "2") (pinfunction "2_2") (pintype "passive"))
    )
    (net (code "20") (name "Net-(MB_PWR-A2)") (class "Default")
      (node (ref "MB_PWR") (pin "2") (pinfunction "A2_2") (pintype "passive"))
      (node (ref "R1") (pin "1") (pinfunction "1_1") (pintype "passive"))
    )
    (net (code "21") (name "Net-(R18-Pad1)") (class "Default")
      (node (ref "R18") (pin "1") (pinfunction "1_1") (pintype "passive"))
      (node (ref "R21") (pin "2") (pinfunction "2_2") (pintype "passive"))
    )
    (net (code "22") (name "Net-(R19-Pad2)") (class "Default")
      (node (ref "R19") (pin "2") (pinfunction "2_2") (pintype "passive"))
      (node (ref "SW1") (pin "3") (pinfunction "3_3") (pintype "power_in"))
    )
    (net (code "23") (name "Net-(R29-Pad1)") (class "Default")
      (node (ref "R29") (pin "1") (pinfunction "1_1") (pintype "passive"))
      (node (ref "R31") (pin "2") (pinfunction "2_2") (pintype "passive"))
    )
    (net (code "24") (name "Net-(R35-Pad2)") (class "Default")
      (node (ref "R35") (pin "2") (pinfunction "2_2") (pintype "passive"))
      (node (ref "SW2") (pin "3") (pinfunction "3_3") (pintype "power_in"))
    )
    (net (code "25") (name "Net-(RB_PW-A2)") (class "Default")
      (node (ref "R36") (pin "1") (pinfunction "1_1") (pintype "passive"))
      (node (ref "RB_PW") (pin "2") (pinfunction "A2_2") (pintype "passive"))
    )
    (net (code "26") (name "Net-(REC_PWR-A2)") (class "Default")
      (node (ref "R37") (pin "1") (pinfunction "1_1") (pintype "passive"))
      (node (ref "REC_PWR") (pin "2") (pinfunction "A2_2") (pintype "passive"))
    )
    (net (code "27") (name "Net-(SS1-A2)") (class "Default")
      (node (ref "R5") (pin "1") (pinfunction "1_1") (pintype "passive"))
      (node (ref "SS1") (pin "2") (pinfunction "A2_2") (pintype "passive"))
    )
    (net (code "28") (name "Net-(SS2-A2)") (class "Default")
      (node (ref "R13") (pin "1") (pinfunction "1_1") (pintype "passive"))
      (node (ref "SS2") (pin "2") (pinfunction "A2_2") (pintype "passive"))
    )
    (net (code "29") (name "Net-(U1-CP2)") (class "Default")
      (node (ref "R23") (pin "1") (pinfunction "1_1") (pintype "passive"))
      (node (ref "R24") (pin "1") (pinfunction "1_1") (pintype "passive"))
      (node (ref "R28") (pin "2") (pinfunction "2_2") (pintype "passive"))
      (node (ref "U1") (pin "3") (pinfunction "CP2_3") (pintype "passive"))
    )
    (net (code "30") (name "Net-(U1-ILIM)") (class "Default")
      (node (ref "R18") (pin "2") (pinfunction "2_2") (pintype "passive"))
      (node (ref "U1") (pin "10") (pinfunction "ILIM_10") (pintype "passive"))
    )
    (net (code "31") (name "Net-(U1-OV1)") (class "Default")
      (node (ref "R2") (pin "1") (pinfunction "1_1") (pintype "passive"))
      (node (ref "R7") (pin "2") (pinfunction "2_2") (pintype "passive"))
      (node (ref "U1") (pin "5") (pinfunction "OV1_5") (pintype "passive"))
    )
    (net (code "32") (name "Net-(U1-OV2)") (class "Default")
      (node (ref "R15") (pin "1") (pinfunction "1_1") (pintype "passive"))
      (node (ref "R20") (pin "2") (pinfunction "2_2") (pintype "passive"))
      (node (ref "U1") (pin "4") (pinfunction "OV2_4") (pintype "passive"))
    )
    (net (code "33") (name "Net-(U1-PR1)") (class "Default")
      (node (ref "R3") (pin "1") (pinfunction "1_1") (pintype "passive"))
      (node (ref "R4") (pin "1") (pinfunction "1_1") (pintype "passive"))
      (node (ref "R6") (pin "2") (pinfunction "2_2") (pintype "passive"))
      (node (ref "U1") (pin "6") (pinfunction "PR1_6") (pintype "passive"))
    )
    (net (code "34") (name "Net-(U1-SS)") (class "Default")
      (node (ref "C2") (pin "2") (pinfunction "2_2") (pintype "passive"))
      (node (ref "U1") (pin "11") (pinfunction "SS_11") (pintype "passive"))
    )
    (net (code "35") (name "Net-(U1-ST)") (class "Default")
      (node (ref "R5") (pin "2") (pinfunction "2_2") (pintype "passive"))
      (node (ref "U1") (pin "9") (pinfunction "ST_9") (pintype "passive"))
    )
    (net (code "36") (name "Net-(U2-CP2)") (class "Default")
      (node (ref "R32") (pin "1") (pinfunction "1_1") (pintype "passive"))
      (node (ref "R33") (pin "1") (pinfunction "1_1") (pintype "passive"))
      (node (ref "R34") (pin "2") (pinfunction "2_2") (pintype "passive"))
      (node (ref "U2") (pin "3") (pinfunction "CP2_3") (pintype "passive"))
    )
    (net (code "37") (name "Net-(U2-ILIM)") (class "Default")
      (node (ref "R29") (pin "2") (pinfunction "2_2") (pintype "passive"))
      (node (ref "U2") (pin "10") (pinfunction "ILIM_10") (pintype "passive"))
    )
    (net (code "38") (name "Net-(U2-IN2)") (class "Default")
      (node (ref "R27") (pin "2") (pinfunction "2_2") (pintype "passive"))
      (node (ref "R32") (pin "2") (pinfunction "2_2") (pintype "passive"))
      (node (ref "R33") (pin "2") (pinfunction "2_2") (pintype "passive"))
      (node (ref "U1") (pin "1") (pinfunction "OUT_1") (pintype "output"))
      (node (ref "U2") (pin "2") (pinfunction "IN2_2") (pintype "input"))
    )
    (net (code "39") (name "Net-(U2-OV1)") (class "Default")
      (node (ref "R10") (pin "1") (pinfunction "1_1") (pintype "passive"))
      (node (ref "R17") (pin "2") (pinfunction "2_2") (pintype "passive"))
      (node (ref "U2") (pin "5") (pinfunction "OV1_5") (pintype "passive"))
    )
    (net (code "40") (name "Net-(U2-OV2)") (class "Default")
      (node (ref "R27") (pin "1") (pinfunction "1_1") (pintype "passive"))
      (node (ref "R30") (pin "2") (pinfunction "2_2") (pintype "passive"))
      (node (ref "U2") (pin "4") (pinfunction "OV2_4") (pintype "passive"))
    )
    (net (code "41") (name "Net-(U2-PR1)") (class "Default")
      (node (ref "R11") (pin "1") (pinfunction "1_1") (pintype "passive"))
      (node (ref "R12") (pin "1") (pinfunction "1_1") (pintype "passive"))
      (node (ref "R16") (pin "2") (pinfunction "2_2") (pintype "passive"))
      (node (ref "U2") (pin "6") (pinfunction "PR1_6") (pintype "passive"))
    )
    (net (code "42") (name "Net-(U2-SS)") (class "Default")
      (node (ref "C3") (pin "2") (pinfunction "2_2") (pintype "passive"))
      (node (ref "U2") (pin "11") (pinfunction "SS_11") (pintype "passive"))
    )
    (net (code "43") (name "Net-(U2-ST)") (class "Default")
      (node (ref "R13") (pin "2") (pinfunction "2_2") (pintype "passive"))
      (node (ref "U2") (pin "9") (pinfunction "ST_9") (pintype "passive"))
    )
    (net (code "44") (name "unconnected-(J1-D-_U2-Pad11)") (class "Default")
      (node (ref "J1") (pin "11") (pinfunction "D-_U2_11") (pintype "bidirectional"))
    )
    (net (code "45") (name "unconnected-(J1-GND_DRAIN_U1-Pad7)") (class "Default")
      (node (ref "J1") (pin "7") (pinfunction "GND_DRAIN_U1_7") (pintype "power_in"))
    )
    (net (code "46") (name "unconnected-(J1-GND_DRAIN_U2-Pad16)") (class "Default")
      (node (ref "J1") (pin "16") (pinfunction "GND_DRAIN_U2_16") (pintype "power_in"))
    )
    (net (code "47") (name "unconnected-(J1-SHIELD-PadS1)") (class "Default")
      (node (ref "J1") (pin "S1") (pinfunction "SHIELD_S1") (pintype "passive"))
    )
    (net (code "48") (name "unconnected-(J1-SHIELD-PadS2)") (class "Default")
      (node (ref "J1") (pin "S2") (pinfunction "SHIELD_S2") (pintype "passive"))
    )
    (net (code "49") (name "unconnected-(J1-SHIELD-PadS3)") (class "Default")
      (node (ref "J1") (pin "S3") (pinfunction "SHIELD_S3") (pintype "passive"))
    )
    (net (code "50") (name "unconnected-(J2-Pad10)") (class "Default")
      (node (ref "J2") (pin "10") (pinfunction "10_10") (pintype "passive"))
    )
    (net (code "51") (name "unconnected-(J2-Pad12)") (class "Default")
      (node (ref "J2") (pin "12") (pinfunction "12_12") (pintype "passive"))
    )
    (net (code "52") (name "unconnected-(J4-Pad3)") (class "Default")
      (node (ref "J4") (pin "3") (pinfunction "3_3") (pintype "passive"))
    )
    (net (code "53") (name "unconnected-(J4-Pad4)") (class "Default")
      (node (ref "J4") (pin "4") (pinfunction "4_4") (pintype "passive"))
    )
    (net (code "54") (name "unconnected-(J5-Pad3)") (class "Default")
      (node (ref "J5") (pin "3") (pinfunction "3_3") (pintype "passive"))
    )
    (net (code "55") (name "unconnected-(J5-Pad4)") (class "Default")
      (node (ref "J5") (pin "4") (pinfunction "4_4") (pintype "passive"))
    )
    (net (code "56") (name "unconnected-(U1-OUT-Pad8)") (class "Default")
      (node (ref "U1") (pin "8") (pinfunction "OUT_8") (pintype "output"))
    )
    (net (code "57") (name "unconnected-(U2-OUT-Pad8)") (class "Default")
      (node (ref "U2") (pin "8") (pinfunction "OUT_8") (pintype "output"))
    )
  )
)
